# SD.net
KiCad netlist of a schematic drawn in EAGLE
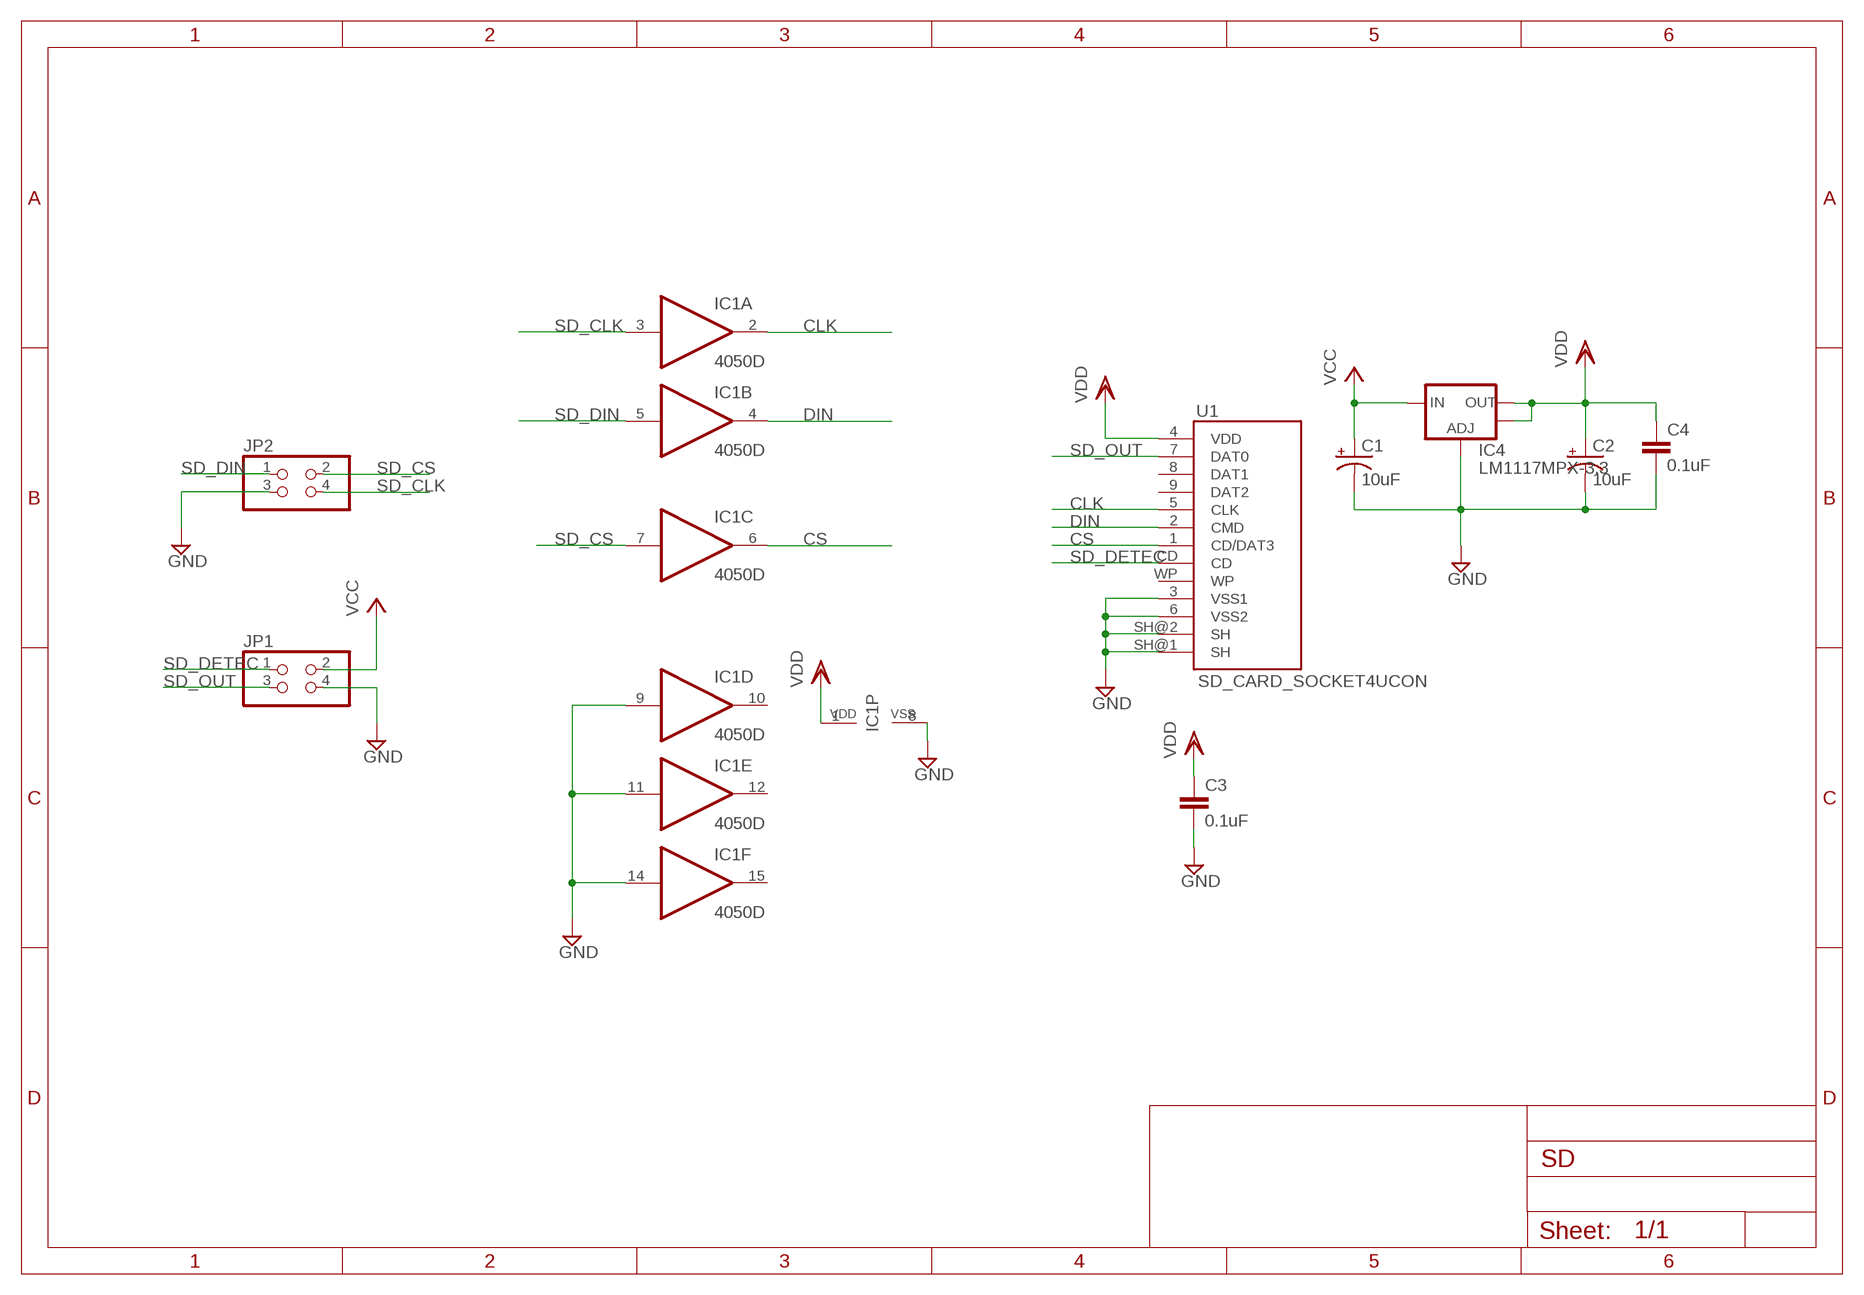
[diagram p0: schematic, sheet 1]

(export (version "E")
  (design (tool "Eeschema 10.0.6"))
  (components
    (comp (ref "C1")
      (value "10uF")
      (footprint "eagle-import:CT3216")
      (libsource (lib "eagle-import") (part "CPOL-USCT3216"))
    )
    (comp (ref "C2")
      (value "10uF")
      (footprint "eagle-import:CT3216")
      (libsource (lib "eagle-import") (part "CPOL-USCT3216"))
    )
    (comp (ref "C3")
      (value "0.1uF")
      (footprint "eagle-import:C0805")
      (libsource (lib "eagle-import") (part "C-EUC0805"))
    )
    (comp (ref "C4")
      (value "0.1uF")
      (footprint "eagle-import:C0805")
      (libsource (lib "eagle-import") (part "C-EUC0805"))
    )
    (comp (ref "IC1")
      (value "4050D")
      (footprint "eagle-import:SO16")
      (libsource (lib "eagle-import") (part "4050D"))
    )
    (comp (ref "IC4")
      (value "LM1117MPX-3.3")
      (footprint "eagle-import:SOT223")
      (libsource (lib "eagle-import") (part "V_REG_LM1117SOT223"))
    )
    (comp (ref "JP1")
      (value "PINHD-2X2")
      (footprint "eagle-import:2X02")
      (libsource (lib "eagle-import") (part "PINHD-2X2"))
    )
    (comp (ref "JP2")
      (value "PINHD-2X2")
      (footprint "eagle-import:2X02")
      (libsource (lib "eagle-import") (part "PINHD-2X2"))
    )
    (comp (ref "U1")
      (value "SD_CARD_SOCKET4UCON")
      (footprint "eagle-import:SDCARD_4UCONN")
      (libsource (lib "eagle-import") (part "SD_CARD_SOCKET4UCON"))
    )
  )
  (nets
    (net (code "1") (name "/CLK") (class "Default")
      (node (ref "IC1") (pin "2") (pinfunction "O_2") (pintype "output"))
      (node (ref "U1") (pin "5") (pinfunction "CLK_5") (pintype "bidirectional"))
    )
    (net (code "2") (name "/CS") (class "Default")
      (node (ref "IC1") (pin "6") (pinfunction "O_6") (pintype "output"))
      (node (ref "U1") (pin "1") (pinfunction "CD/DAT3_1") (pintype "bidirectional"))
    )
    (net (code "3") (name "/DIN") (class "Default")
      (node (ref "IC1") (pin "4") (pinfunction "O_4") (pintype "output"))
      (node (ref "U1") (pin "2") (pinfunction "CMD_2") (pintype "bidirectional"))
    )
    (net (code "4") (name "/SD_CLK") (class "Default")
      (node (ref "IC1") (pin "3") (pinfunction "I_3") (pintype "input"))
      (node (ref "JP2") (pin "4") (pinfunction "4_4") (pintype "passive"))
    )
    (net (code "5") (name "/SD_CS") (class "Default")
      (node (ref "IC1") (pin "7") (pinfunction "I_7") (pintype "input"))
      (node (ref "JP2") (pin "2") (pinfunction "2_2") (pintype "passive"))
    )
    (net (code "6") (name "/SD_DETEC") (class "Default")
      (node (ref "JP1") (pin "1") (pinfunction "1_1") (pintype "passive"))
      (node (ref "U1") (pin "CD") (pinfunction "CD_CD") (pintype "bidirectional"))
    )
    (net (code "7") (name "/SD_DIN") (class "Default")
      (node (ref "IC1") (pin "5") (pinfunction "I_5") (pintype "input"))
      (node (ref "JP2") (pin "1") (pinfunction "1_1") (pintype "passive"))
    )
    (net (code "8") (name "/SD_OUT") (class "Default")
      (node (ref "JP1") (pin "3") (pinfunction "3_3") (pintype "passive"))
      (node (ref "U1") (pin "7") (pinfunction "DAT0_7") (pintype "bidirectional"))
    )
    (net (code "9") (name "GND") (class "Default")
      (node (ref "C1") (pin "-") (pinfunction "-_-") (pintype "passive"))
      (node (ref "C2") (pin "-") (pinfunction "-_-") (pintype "passive"))
      (node (ref "C3") (pin "2") (pinfunction "2_2") (pintype "passive"))
      (node (ref "C4") (pin "2") (pinfunction "2_2") (pintype "passive"))
      (node (ref "IC1") (pin "11") (pinfunction "I_11") (pintype "input"))
      (node (ref "IC1") (pin "14") (pinfunction "I_14") (pintype "input"))
      (node (ref "IC1") (pin "8") (pinfunction "VSS_8") (pintype "power_in"))
      (node (ref "IC1") (pin "9") (pinfunction "I_9") (pintype "input"))
      (node (ref "IC4") (pin "1") (pinfunction "ADJ_1") (pintype "input"))
      (node (ref "JP1") (pin "4") (pinfunction "4_4") (pintype "passive"))
      (node (ref "JP2") (pin "3") (pinfunction "3_3") (pintype "passive"))
      (node (ref "U1") (pin "3") (pinfunction "VSS1_3") (pintype "power_in"))
      (node (ref "U1") (pin "6") (pinfunction "VSS2_6") (pintype "power_in"))
      (node (ref "U1") (pin "SH@1") (pinfunction "SH_SH@1") (pintype "bidirectional"))
      (node (ref "U1") (pin "SH@2") (pinfunction "SH_SH@2") (pintype "bidirectional"))
    )
    (net (code "10") (name "VCC") (class "Default")
      (node (ref "C1") (pin "+") (pinfunction "+_+") (pintype "passive"))
      (node (ref "IC4") (pin "3") (pinfunction "IN_3") (pintype "input"))
      (node (ref "JP1") (pin "2") (pinfunction "2_2") (pintype "passive"))
    )
    (net (code "11") (name "VDD") (class "Default")
      (node (ref "C2") (pin "+") (pinfunction "+_+") (pintype "passive"))
      (node (ref "C3") (pin "1") (pinfunction "1_1") (pintype "passive"))
      (node (ref "C4") (pin "1") (pinfunction "1_1") (pintype "passive"))
      (node (ref "IC1") (pin "1") (pinfunction "VDD_1") (pintype "power_in"))
      (node (ref "IC4") (pin "2") (pinfunction "OUT_2") (pintype "output"))
      (node (ref "IC4") (pin "4") (pinfunction "OUT_4") (pintype "output"))
      (node (ref "U1") (pin "4") (pinfunction "VDD_4") (pintype "power_in"))
    )
    (net (code "12") (name "unconnected-(IC1D-O-Pad10)") (class "Default")
      (node (ref "IC1") (pin "10") (pinfunction "O_10") (pintype "output"))
    )
    (net (code "13") (name "unconnected-(IC1E-O-Pad12)") (class "Default")
      (node (ref "IC1") (pin "12") (pinfunction "O_12") (pintype "output"))
    )
    (net (code "14") (name "unconnected-(IC1F-O-Pad15)") (class "Default")
      (node (ref "IC1") (pin "15") (pinfunction "O_15") (pintype "output"))
    )
    (net (code "15") (name "unconnected-(U1-DAT1-Pad8)") (class "Default")
      (node (ref "U1") (pin "8") (pinfunction "DAT1_8") (pintype "bidirectional"))
    )
    (net (code "16") (name "unconnected-(U1-DAT2-Pad9)") (class "Default")
      (node (ref "U1") (pin "9") (pinfunction "DAT2_9") (pintype "bidirectional"))
    )
    (net (code "17") (name "unconnected-(U1-PadWP)") (class "Default")
      (node (ref "U1") (pin "WP") (pinfunction "WP_WP") (pintype "bidirectional"))
    )
  )
)
